# BlueToothi.net
KiCad netlist of a schematic drawn in Altium Designer
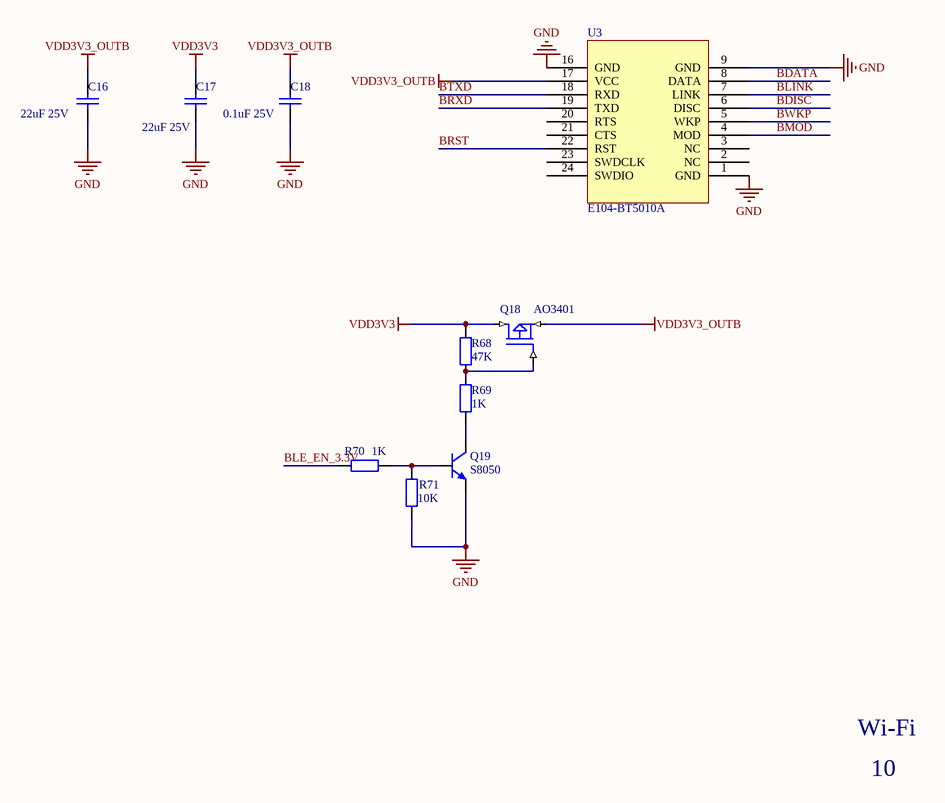
[diagram p0: BlueToothi.SchDoc]

(export (version "E")
  (design (tool "Eeschema 10.0.6"))
  (components
    (comp (ref "C16")
      (value "22uF 25V")
      (footprint "SMD-0805C")
      (description "贴片电容 20%")
      (libsource (lib "XiaoyI") (part "CAP4"))
    )
    (comp (ref "C17")
      (value "22uF 25V")
      (footprint "SMD-0805C")
      (description "贴片电容 20%")
      (libsource (lib "XiaoyI") (part "CAP4"))
    )
    (comp (ref "C18")
      (value "0.1uF 25V")
      (footprint "SMD-0805C")
      (description "贴片电容 20%")
      (libsource (lib "XiaoyI") (part "CAP4"))
    )
    (comp (ref "Q18")
      (value "AO3401")
      (footprint "SOT-23")
      (description "MOSFET P")
      (libsource (lib "ABB") (part "MOSFET P"))
    )
    (comp (ref "Q19")
      (value "S8050")
      (footprint "SOT-23")
      (description "NPN")
      (libsource (lib "XiaoyI") (part "NPN-1"))
    )
    (comp (ref "R68")
      (value "47K")
      (footprint "SMD-0603")
      (description "贴片电阻 5%")
      (libsource (lib "XiaoyI") (part "RES2"))
    )
    (comp (ref "R69")
      (value "1K")
      (footprint "SMD-0603")
      (description "贴片电阻 5%")
      (libsource (lib "") (part "RES2_1"))
    )
    (comp (ref "R70")
      (value "1K")
      (footprint "SMD-0603")
      (description "贴片电阻 5%")
      (libsource (lib "") (part "RES2_2"))
    )
    (comp (ref "R71")
      (value "10K")
      (footprint "SMD-0603")
      (description "贴片电阻 5%")
      (libsource (lib "") (part "RES2_1"))
    )
    (comp (ref "U3")
      (value "E104-BT5010A")
      (footprint "E104-BT503")
      (description "E104-BT503")
      (libsource (lib "stm32") (part "E104-BT503"))
    )
  )
  (nets
    (net (code "1") (name "/BDATA") (class "Default")
      (node (ref "U3") (pin "8") (pinfunction "DATA_8") (pintype "passive"))
    )
    (net (code "2") (name "/BDISC") (class "Default")
      (node (ref "U3") (pin "6") (pinfunction "DISC_6") (pintype "passive"))
    )
    (net (code "3") (name "/BLE_EN_3.3V") (class "Default")
      (node (ref "R70") (pin "1") (pinfunction "1_1") (pintype "passive"))
    )
    (net (code "4") (name "/BLINK") (class "Default")
      (node (ref "U3") (pin "7") (pinfunction "LINK_7") (pintype "passive"))
    )
    (net (code "5") (name "/BMOD") (class "Default")
      (node (ref "U3") (pin "4") (pinfunction "MOD_4") (pintype "passive"))
    )
    (net (code "6") (name "/BRST") (class "Default")
      (node (ref "U3") (pin "22") (pinfunction "RST_22") (pintype "passive"))
    )
    (net (code "7") (name "/BRXD") (class "Default")
      (node (ref "U3") (pin "19") (pinfunction "TXD_19") (pintype "passive"))
    )
    (net (code "8") (name "/BTXD") (class "Default")
      (node (ref "U3") (pin "18") (pinfunction "RXD_18") (pintype "passive"))
    )
    (net (code "9") (name "/BWKP") (class "Default")
      (node (ref "U3") (pin "5") (pinfunction "WKP_5") (pintype "passive"))
    )
    (net (code "10") (name "GND") (class "Default")
      (node (ref "C16") (pin "1") (pinfunction "1_1") (pintype "passive"))
      (node (ref "C17") (pin "1") (pinfunction "1_1") (pintype "passive"))
      (node (ref "C18") (pin "1") (pinfunction "1_1") (pintype "passive"))
      (node (ref "Q19") (pin "2") (pinfunction "E_2") (pintype "passive"))
      (node (ref "R71") (pin "1") (pinfunction "1_1") (pintype "passive"))
      (node (ref "U3") (pin "1") (pinfunction "GND_1") (pintype "passive"))
      (node (ref "U3") (pin "16") (pinfunction "GND_16") (pintype "passive"))
      (node (ref "U3") (pin "9") (pinfunction "GND_9") (pintype "passive"))
    )
    (net (code "11") (name "Net-(Q18-G)") (class "Default")
      (node (ref "Q18") (pin "1") (pinfunction "G_1") (pintype "input"))
      (node (ref "R68") (pin "2") (pinfunction "2_2") (pintype "passive"))
      (node (ref "R69") (pin "2") (pinfunction "2_2") (pintype "passive"))
    )
    (net (code "12") (name "Net-(Q19-B)") (class "Default")
      (node (ref "Q19") (pin "1") (pinfunction "B_1") (pintype "passive"))
      (node (ref "R70") (pin "2") (pinfunction "2_2") (pintype "passive"))
      (node (ref "R71") (pin "2") (pinfunction "2_2") (pintype "passive"))
    )
    (net (code "13") (name "Net-(Q19-C)") (class "Default")
      (node (ref "Q19") (pin "3") (pinfunction "C_3") (pintype "passive"))
      (node (ref "R69") (pin "1") (pinfunction "1_1") (pintype "passive"))
    )
    (net (code "14") (name "VDD3V3") (class "Default")
      (node (ref "C17") (pin "2") (pinfunction "2_2") (pintype "passive"))
      (node (ref "Q18") (pin "2") (pinfunction "D_2") (pintype "input"))
      (node (ref "R68") (pin "1") (pinfunction "1_1") (pintype "passive"))
    )
    (net (code "15") (name "VDD3V3_OUTB") (class "Default")
      (node (ref "C16") (pin "2") (pinfunction "2_2") (pintype "passive"))
      (node (ref "C18") (pin "2") (pinfunction "2_2") (pintype "passive"))
      (node (ref "Q18") (pin "3") (pinfunction "S_3") (pintype "input"))
      (node (ref "U3") (pin "17") (pinfunction "VCC_17") (pintype "passive"))
    )
    (net (code "16") (name "unconnected-(U3-CTS-Pad21)") (class "Default")
      (node (ref "U3") (pin "21") (pinfunction "CTS_21") (pintype "passive"))
    )
    (net (code "17") (name "unconnected-(U3-NC-Pad2)") (class "Default")
      (node (ref "U3") (pin "2") (pinfunction "NC_2") (pintype "passive"))
    )
    (net (code "18") (name "unconnected-(U3-NC-Pad3)") (class "Default")
      (node (ref "U3") (pin "3") (pinfunction "NC_3") (pintype "passive"))
    )
    (net (code "19") (name "unconnected-(U3-RTS-Pad20)") (class "Default")
      (node (ref "U3") (pin "20") (pinfunction "RTS_20") (pintype "passive"))
    )
    (net (code "20") (name "unconnected-(U3-SWDCLK-Pad23)") (class "Default")
      (node (ref "U3") (pin "23") (pinfunction "SWDCLK_23") (pintype "passive"))
    )
    (net (code "21") (name "unconnected-(U3-SWDIO-Pad24)") (class "Default")
      (node (ref "U3") (pin "24") (pinfunction "SWDIO_24") (pintype "passive"))
    )
  )
)
